# PCB_PSOC.net
KiCad netlist of a schematic drawn in EAGLE
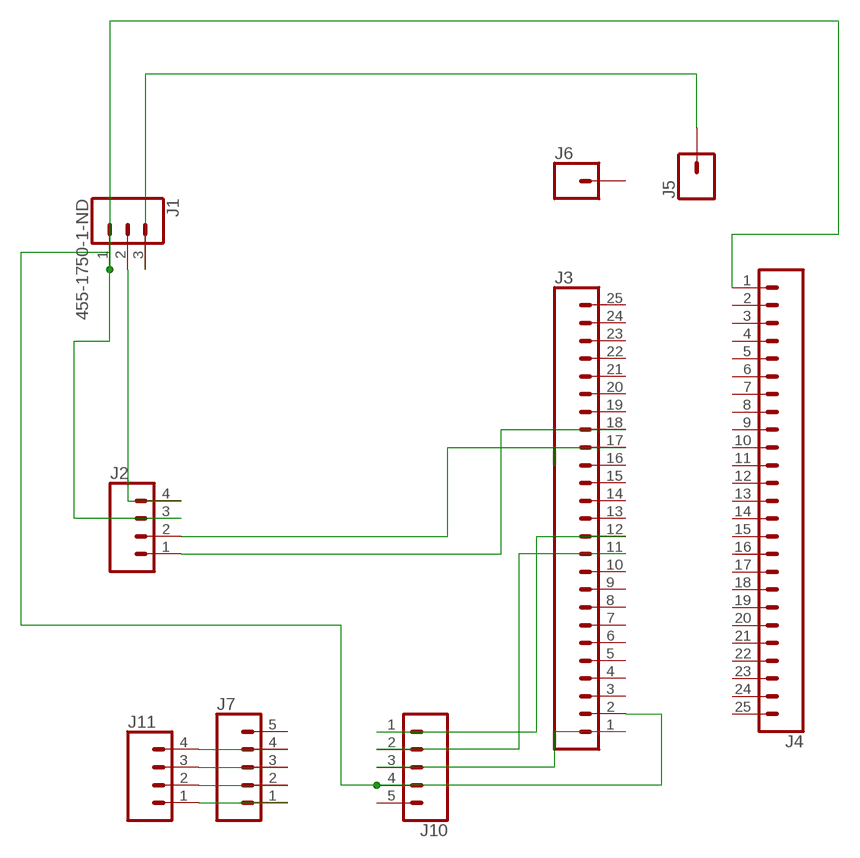
[diagram p0: schematic, sheet 1]

(export (version "E")
  (design (tool "Eeschema 10.0.6"))
  (components
    (comp (ref "J1")
      (value "455-1750-1-ND")
      (footprint "eagle-import:1X03")
      (libsource (lib "eagle-import") (part "CONN_03"))
    )
    (comp (ref "J2")
      (value "CONN_04PTH")
      (footprint "eagle-import:1X04")
      (libsource (lib "eagle-import") (part "CONN_04PTH"))
    )
    (comp (ref "J3")
      (value "CONN_25")
      (footprint "eagle-import:1X25")
      (libsource (lib "eagle-import") (part "CONN_25"))
    )
    (comp (ref "J4")
      (value "CONN_25")
      (footprint "eagle-import:1X25")
      (libsource (lib "eagle-import") (part "CONN_25"))
    )
    (comp (ref "J5")
      (value "CONN_01")
      (footprint "eagle-import:1X01")
      (libsource (lib "eagle-import") (part "CONN_01"))
    )
    (comp (ref "J6")
      (value "CONN_01")
      (footprint "eagle-import:1X01")
      (libsource (lib "eagle-import") (part "CONN_01"))
    )
    (comp (ref "J7")
      (value "CONN_05")
      (footprint "eagle-import:1X05")
      (libsource (lib "eagle-import") (part "CONN_05"))
    )
    (comp (ref "J10")
      (value "CONN_05")
      (footprint "eagle-import:1X05")
      (libsource (lib "eagle-import") (part "CONN_05"))
    )
    (comp (ref "J11")
      (value "CONN_04PTH")
      (footprint "eagle-import:1X04")
      (libsource (lib "eagle-import") (part "CONN_04PTH"))
    )
  )
  (nets
    (net (code "1") (name "Net-(J1-Pad1)") (class "Default")
      (node (ref "J1") (pin "1") (pinfunction "1_1") (pintype "passive"))
      (node (ref "J10") (pin "4") (pinfunction "4_4") (pintype "passive"))
      (node (ref "J2") (pin "3") (pinfunction "3_3") (pintype "passive"))
      (node (ref "J3") (pin "2") (pinfunction "2_2") (pintype "passive"))
      (node (ref "J4") (pin "1") (pinfunction "1_1") (pintype "passive"))
    )
    (net (code "2") (name "Net-(J1-Pad2)") (class "Default")
      (node (ref "J1") (pin "2") (pinfunction "2_2") (pintype "passive"))
      (node (ref "J2") (pin "4") (pinfunction "4_4") (pintype "passive"))
    )
    (net (code "3") (name "Net-(J1-Pad3)") (class "Default")
      (node (ref "J1") (pin "3") (pinfunction "3_3") (pintype "passive"))
      (node (ref "J5") (pin "1") (pinfunction "1_1") (pintype "passive"))
    )
    (net (code "4") (name "Net-(J2-Pad1)") (class "Default")
      (node (ref "J2") (pin "1") (pinfunction "1_1") (pintype "passive"))
      (node (ref "J3") (pin "18") (pinfunction "18_18") (pintype "passive"))
    )
    (net (code "5") (name "Net-(J2-Pad2)") (class "Default")
      (node (ref "J2") (pin "2") (pinfunction "2_2") (pintype "passive"))
      (node (ref "J3") (pin "17") (pinfunction "17_17") (pintype "passive"))
    )
    (net (code "6") (name "Net-(J10-Pad1)") (class "Default")
      (node (ref "J10") (pin "1") (pinfunction "1_1") (pintype "passive"))
      (node (ref "J3") (pin "12") (pinfunction "12_12") (pintype "passive"))
    )
    (net (code "7") (name "Net-(J10-Pad2)") (class "Default")
      (node (ref "J10") (pin "2") (pinfunction "2_2") (pintype "passive"))
      (node (ref "J3") (pin "11") (pinfunction "11_11") (pintype "passive"))
    )
    (net (code "8") (name "Net-(J10-Pad3)") (class "Default")
      (node (ref "J10") (pin "3") (pinfunction "3_3") (pintype "passive"))
      (node (ref "J3") (pin "1") (pinfunction "1_1") (pintype "passive"))
    )
    (net (code "9") (name "Net-(J11-Pad1)") (class "Default")
      (node (ref "J11") (pin "1") (pinfunction "1_1") (pintype "passive"))
      (node (ref "J7") (pin "1") (pinfunction "1_1") (pintype "passive"))
    )
    (net (code "10") (name "Net-(J11-Pad2)") (class "Default")
      (node (ref "J11") (pin "2") (pinfunction "2_2") (pintype "passive"))
      (node (ref "J7") (pin "2") (pinfunction "2_2") (pintype "passive"))
    )
    (net (code "11") (name "Net-(J11-Pad3)") (class "Default")
      (node (ref "J11") (pin "3") (pinfunction "3_3") (pintype "passive"))
      (node (ref "J7") (pin "3") (pinfunction "3_3") (pintype "passive"))
    )
    (net (code "12") (name "Net-(J11-Pad4)") (class "Default")
      (node (ref "J11") (pin "4") (pinfunction "4_4") (pintype "passive"))
      (node (ref "J7") (pin "4") (pinfunction "4_4") (pintype "passive"))
    )
    (net (code "13") (name "unconnected-(J3-Pad3)") (class "Default")
      (node (ref "J3") (pin "3") (pinfunction "3_3") (pintype "passive"))
    )
    (net (code "14") (name "unconnected-(J3-Pad4)") (class "Default")
      (node (ref "J3") (pin "4") (pinfunction "4_4") (pintype "passive"))
    )
    (net (code "15") (name "unconnected-(J3-Pad5)") (class "Default")
      (node (ref "J3") (pin "5") (pinfunction "5_5") (pintype "passive"))
    )
    (net (code "16") (name "unconnected-(J3-Pad6)") (class "Default")
      (node (ref "J3") (pin "6") (pinfunction "6_6") (pintype "passive"))
    )
    (net (code "17") (name "unconnected-(J3-Pad7)") (class "Default")
      (node (ref "J3") (pin "7") (pinfunction "7_7") (pintype "passive"))
    )
    (net (code "18") (name "unconnected-(J3-Pad8)") (class "Default")
      (node (ref "J3") (pin "8") (pinfunction "8_8") (pintype "passive"))
    )
    (net (code "19") (name "unconnected-(J3-Pad9)") (class "Default")
      (node (ref "J3") (pin "9") (pinfunction "9_9") (pintype "passive"))
    )
    (net (code "20") (name "unconnected-(J3-Pad10)") (class "Default")
      (node (ref "J3") (pin "10") (pinfunction "10_10") (pintype "passive"))
    )
    (net (code "21") (name "unconnected-(J3-Pad13)") (class "Default")
      (node (ref "J3") (pin "13") (pinfunction "13_13") (pintype "passive"))
    )
    (net (code "22") (name "unconnected-(J3-Pad14)") (class "Default")
      (node (ref "J3") (pin "14") (pinfunction "14_14") (pintype "passive"))
    )
    (net (code "23") (name "unconnected-(J3-Pad15)") (class "Default")
      (node (ref "J3") (pin "15") (pinfunction "15_15") (pintype "passive"))
    )
    (net (code "24") (name "unconnected-(J3-Pad16)") (class "Default")
      (node (ref "J3") (pin "16") (pinfunction "16_16") (pintype "passive"))
    )
    (net (code "25") (name "unconnected-(J3-Pad19)") (class "Default")
      (node (ref "J3") (pin "19") (pinfunction "19_19") (pintype "passive"))
    )
    (net (code "26") (name "unconnected-(J3-Pad20)") (class "Default")
      (node (ref "J3") (pin "20") (pinfunction "20_20") (pintype "passive"))
    )
    (net (code "27") (name "unconnected-(J3-Pad21)") (class "Default")
      (node (ref "J3") (pin "21") (pinfunction "21_21") (pintype "passive"))
    )
    (net (code "28") (name "unconnected-(J3-Pad22)") (class "Default")
      (node (ref "J3") (pin "22") (pinfunction "22_22") (pintype "passive"))
    )
    (net (code "29") (name "unconnected-(J3-Pad23)") (class "Default")
      (node (ref "J3") (pin "23") (pinfunction "23_23") (pintype "passive"))
    )
    (net (code "30") (name "unconnected-(J3-Pad24)") (class "Default")
      (node (ref "J3") (pin "24") (pinfunction "24_24") (pintype "passive"))
    )
    (net (code "31") (name "unconnected-(J3-Pad25)") (class "Default")
      (node (ref "J3") (pin "25") (pinfunction "25_25") (pintype "passive"))
    )
    (net (code "32") (name "unconnected-(J4-Pad2)") (class "Default")
      (node (ref "J4") (pin "2") (pinfunction "2_2") (pintype "passive"))
    )
    (net (code "33") (name "unconnected-(J4-Pad3)") (class "Default")
      (node (ref "J4") (pin "3") (pinfunction "3_3") (pintype "passive"))
    )
    (net (code "34") (name "unconnected-(J4-Pad4)") (class "Default")
      (node (ref "J4") (pin "4") (pinfunction "4_4") (pintype "passive"))
    )
    (net (code "35") (name "unconnected-(J4-Pad5)") (class "Default")
      (node (ref "J4") (pin "5") (pinfunction "5_5") (pintype "passive"))
    )
    (net (code "36") (name "unconnected-(J4-Pad6)") (class "Default")
      (node (ref "J4") (pin "6") (pinfunction "6_6") (pintype "passive"))
    )
    (net (code "37") (name "unconnected-(J4-Pad7)") (class "Default")
      (node (ref "J4") (pin "7") (pinfunction "7_7") (pintype "passive"))
    )
    (net (code "38") (name "unconnected-(J4-Pad8)") (class "Default")
      (node (ref "J4") (pin "8") (pinfunction "8_8") (pintype "passive"))
    )
    (net (code "39") (name "unconnected-(J4-Pad9)") (class "Default")
      (node (ref "J4") (pin "9") (pinfunction "9_9") (pintype "passive"))
    )
    (net (code "40") (name "unconnected-(J4-Pad10)") (class "Default")
      (node (ref "J4") (pin "10") (pinfunction "10_10") (pintype "passive"))
    )
    (net (code "41") (name "unconnected-(J4-Pad11)") (class "Default")
      (node (ref "J4") (pin "11") (pinfunction "11_11") (pintype "passive"))
    )
    (net (code "42") (name "unconnected-(J4-Pad12)") (class "Default")
      (node (ref "J4") (pin "12") (pinfunction "12_12") (pintype "passive"))
    )
    (net (code "43") (name "unconnected-(J4-Pad13)") (class "Default")
      (node (ref "J4") (pin "13") (pinfunction "13_13") (pintype "passive"))
    )
    (net (code "44") (name "unconnected-(J4-Pad14)") (class "Default")
      (node (ref "J4") (pin "14") (pinfunction "14_14") (pintype "passive"))
    )
    (net (code "45") (name "unconnected-(J4-Pad15)") (class "Default")
      (node (ref "J4") (pin "15") (pinfunction "15_15") (pintype "passive"))
    )
    (net (code "46") (name "unconnected-(J4-Pad16)") (class "Default")
      (node (ref "J4") (pin "16") (pinfunction "16_16") (pintype "passive"))
    )
    (net (code "47") (name "unconnected-(J4-Pad17)") (class "Default")
      (node (ref "J4") (pin "17") (pinfunction "17_17") (pintype "passive"))
    )
    (net (code "48") (name "unconnected-(J4-Pad18)") (class "Default")
      (node (ref "J4") (pin "18") (pinfunction "18_18") (pintype "passive"))
    )
    (net (code "49") (name "unconnected-(J4-Pad19)") (class "Default")
      (node (ref "J4") (pin "19") (pinfunction "19_19") (pintype "passive"))
    )
    (net (code "50") (name "unconnected-(J4-Pad20)") (class "Default")
      (node (ref "J4") (pin "20") (pinfunction "20_20") (pintype "passive"))
    )
    (net (code "51") (name "unconnected-(J4-Pad21)") (class "Default")
      (node (ref "J4") (pin "21") (pinfunction "21_21") (pintype "passive"))
    )
    (net (code "52") (name "unconnected-(J4-Pad22)") (class "Default")
      (node (ref "J4") (pin "22") (pinfunction "22_22") (pintype "passive"))
    )
    (net (code "53") (name "unconnected-(J4-Pad23)") (class "Default")
      (node (ref "J4") (pin "23") (pinfunction "23_23") (pintype "passive"))
    )
    (net (code "54") (name "unconnected-(J4-Pad24)") (class "Default")
      (node (ref "J4") (pin "24") (pinfunction "24_24") (pintype "passive"))
    )
    (net (code "55") (name "unconnected-(J4-Pad25)") (class "Default")
      (node (ref "J4") (pin "25") (pinfunction "25_25") (pintype "passive"))
    )
    (net (code "56") (name "unconnected-(J6-Pad1)") (class "Default")
      (node (ref "J6") (pin "1") (pinfunction "1_1") (pintype "passive"))
    )
    (net (code "57") (name "unconnected-(J7-Pad5)") (class "Default")
      (node (ref "J7") (pin "5") (pinfunction "5_5") (pintype "passive"))
    )
    (net (code "58") (name "unconnected-(J10-Pad5)") (class "Default")
      (node (ref "J10") (pin "5") (pinfunction "5_5") (pintype "passive"))
    )
  )
)
